# MB_RELAY.net
KiCad netlist of a schematic drawn in Altium Designer
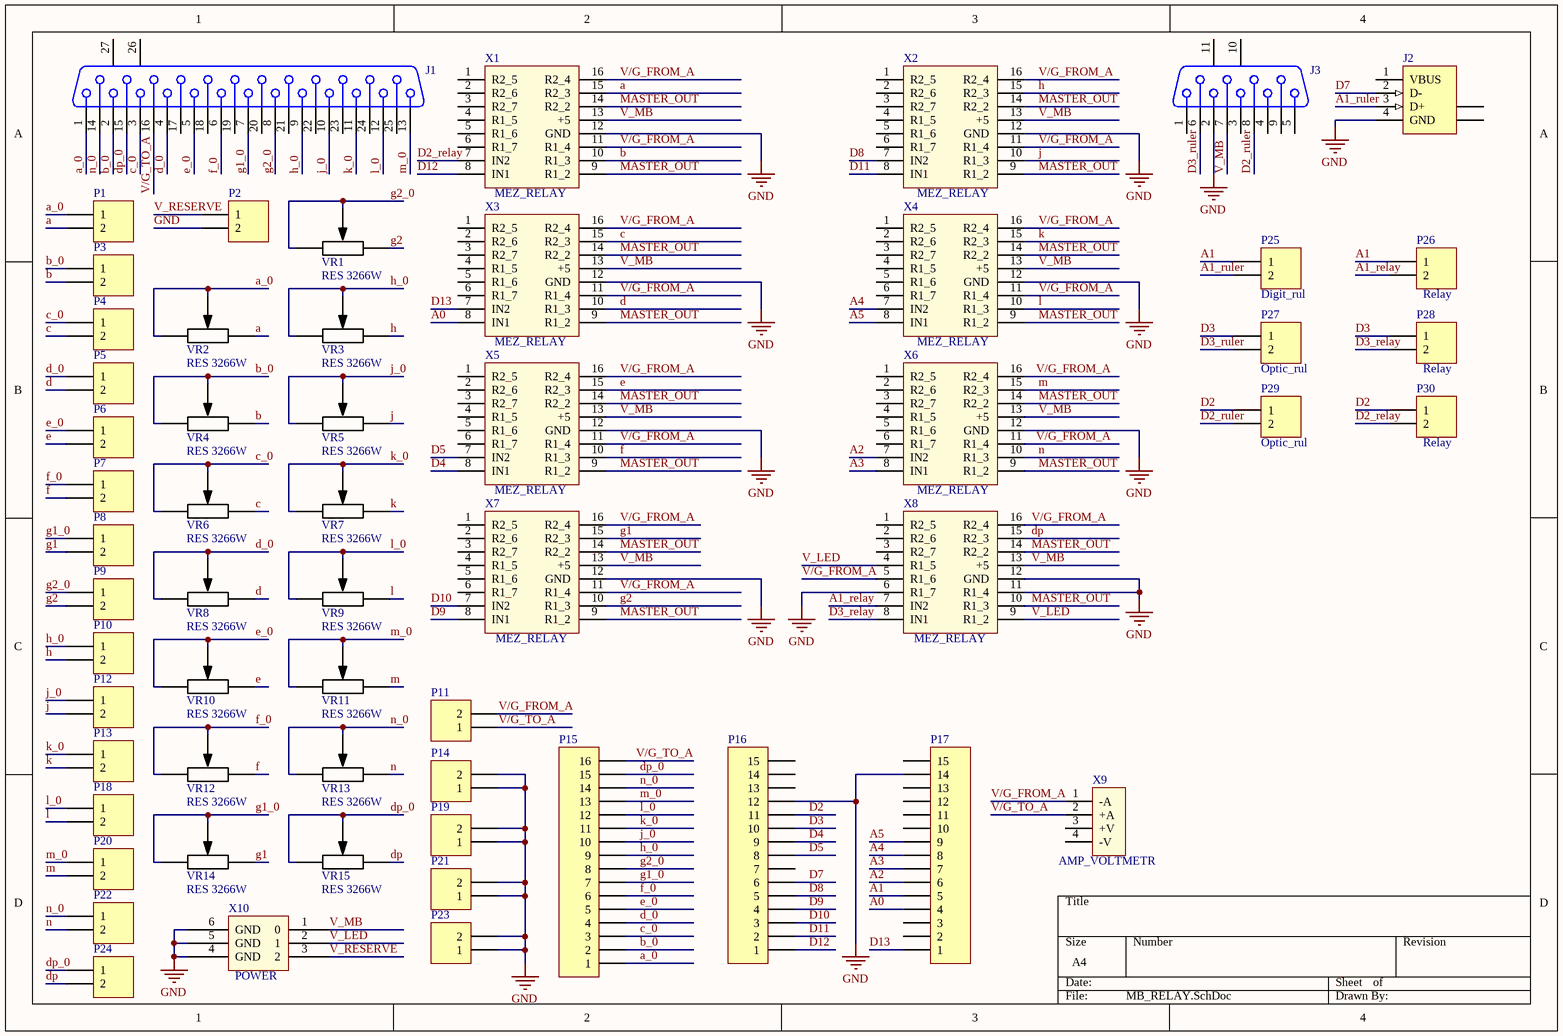
[diagram p0: MB_RELAY.SchDoc]

(export (version "E")
  (design (tool "Eeschema 10.0.6"))
  (components
    (comp (ref "J1")
      (value "D Connector 25")
      (footprint "DSUB1.385-2H25A")
      (description "Receptacle Assembly, 25 Position, Right Angle")
      (fields (field (name "PUBLISHER") "Altium Limited"))
      (libsource (lib "Miscellaneous Connectors") (part "D Connector 25"))
    )
    (comp (ref "J2")
      (value "1-353576-1")
      (footprint "353576")
      (description "USB 1.1, Right Angle, SMT, A Type, Receptacle, 4 Position, White")
      (fields (field (name "PUBLISHER") "Altium Limited"))
      (libsource (lib "AMP Serial Bus USB") (part "1-353576-1"))
    )
    (comp (ref "J3")
      (value "D Connector 9")
      (footprint "DSUB1.385-2H9")
      (description "Receptacle Assembly, 9 Position, Right Angle")
      (fields (field (name "PUBLISHER") "Altium Limited"))
      (libsource (lib "Miscellaneous Connectors") (part "D Connector 9"))
    )
    (comp (ref "P1")
      (value "Header 2")
      (footprint "HDR1X2")
      (description "Header, 2-Pin")
      (fields (field (name "PUBLISHER") "Altium Limited"))
      (libsource (lib "Miscellaneous Connectors") (part "Header 2"))
    )
    (comp (ref "P2")
      (value "Header 2")
      (footprint "HDR1X2")
      (description "Header, 2-Pin")
      (fields (field (name "PUBLISHER") "Altium Limited"))
      (libsource (lib "Miscellaneous Connectors") (part "Header 2"))
    )
    (comp (ref "P3")
      (value "Header 2")
      (footprint "HDR1X2")
      (description "Header, 2-Pin")
      (fields (field (name "PUBLISHER") "Altium Limited"))
      (libsource (lib "Miscellaneous Connectors") (part "Header 2"))
    )
    (comp (ref "P4")
      (value "Header 2")
      (footprint "HDR1X2")
      (description "Header, 2-Pin")
      (fields (field (name "PUBLISHER") "Altium Limited"))
      (libsource (lib "Miscellaneous Connectors") (part "Header 2"))
    )
    (comp (ref "P5")
      (value "Header 2")
      (footprint "HDR1X2")
      (description "Header, 2-Pin")
      (fields (field (name "PUBLISHER") "Altium Limited"))
      (libsource (lib "Miscellaneous Connectors") (part "Header 2"))
    )
    (comp (ref "P6")
      (value "GND")
      (footprint "HDR1X2")
      (description "Header, 2-Pin")
      (fields (field (name "PUBLISHER") "Altium Limited"))
      (libsource (lib "Miscellaneous Connectors") (part "Header 2"))
    )
    (comp (ref "P7")
      (value "GND")
      (footprint "HDR1X2")
      (description "Header, 2-Pin")
      (fields (field (name "PUBLISHER") "Altium Limited"))
      (libsource (lib "Miscellaneous Connectors") (part "Header 2"))
    )
    (comp (ref "P8")
      (value "GND")
      (footprint "HDR1X2")
      (description "Header, 2-Pin")
      (fields (field (name "PUBLISHER") "Altium Limited"))
      (libsource (lib "Miscellaneous Connectors") (part "Header 2"))
    )
    (comp (ref "P9")
      (value "GND")
      (footprint "HDR1X2")
      (description "Header, 2-Pin")
      (fields (field (name "PUBLISHER") "Altium Limited"))
      (libsource (lib "Miscellaneous Connectors") (part "Header 2"))
    )
    (comp (ref "P10")
      (value "Header 2")
      (footprint "HDR1X2")
      (description "Header, 2-Pin")
      (fields (field (name "PUBLISHER") "Altium Limited"))
      (libsource (lib "Miscellaneous Connectors") (part "Header 2"))
    )
    (comp (ref "P11")
      (value "Header 2")
      (footprint "HDR1X2")
      (description "Header, 2-Pin")
      (fields (field (name "PUBLISHER") "Altium Limited"))
      (libsource (lib "") (part "Header 2_1"))
    )
    (comp (ref "P12")
      (value "Header 2")
      (footprint "HDR1X2")
      (description "Header, 2-Pin")
      (fields (field (name "PUBLISHER") "Altium Limited"))
      (libsource (lib "Miscellaneous Connectors") (part "Header 2"))
    )
    (comp (ref "P13")
      (value "GND")
      (footprint "HDR1X2")
      (description "Header, 2-Pin")
      (fields (field (name "PUBLISHER") "Altium Limited"))
      (libsource (lib "Miscellaneous Connectors") (part "Header 2"))
    )
    (comp (ref "P14")
      (value "GND")
      (footprint "HDR1X2")
      (description "Header, 2-Pin")
      (fields (field (name "PUBLISHER") "Altium Limited"))
      (libsource (lib "") (part "Header 2_1"))
    )
    (comp (ref "P15")
      (value "Header 16")
      (footprint "HDR1X16")
      (description "Header, 16-Pin")
      (fields (field (name "PUBLISHER") "Altium Limited"))
      (libsource (lib "Miscellaneous Connectors") (part "Header 16"))
    )
    (comp (ref "P16")
      (value "Header 15")
      (footprint "HDR1X15")
      (description "Header, 15-Pin")
      (fields (field (name "PUBLISHER") "Altium Limited"))
      (libsource (lib "") (part "Header 15_1"))
    )
    (comp (ref "P17")
      (value "Header 15")
      (footprint "HDR1X15")
      (description "Header, 15-Pin")
      (fields (field (name "PUBLISHER") "Altium Limited"))
      (libsource (lib "Miscellaneous Connectors") (part "Header 15"))
    )
    (comp (ref "P18")
      (value "GND")
      (footprint "HDR1X2")
      (description "Header, 2-Pin")
      (fields (field (name "PUBLISHER") "Altium Limited"))
      (libsource (lib "Miscellaneous Connectors") (part "Header 2"))
    )
    (comp (ref "P19")
      (value "GND")
      (footprint "HDR1X2")
      (description "Header, 2-Pin")
      (fields (field (name "PUBLISHER") "Altium Limited"))
      (libsource (lib "") (part "Header 2_1"))
    )
    (comp (ref "P20")
      (value "GND")
      (footprint "HDR1X2")
      (description "Header, 2-Pin")
      (fields (field (name "PUBLISHER") "Altium Limited"))
      (libsource (lib "Miscellaneous Connectors") (part "Header 2"))
    )
    (comp (ref "P21")
      (value "GND")
      (footprint "HDR1X2")
      (description "Header, 2-Pin")
      (fields (field (name "PUBLISHER") "Altium Limited"))
      (libsource (lib "") (part "Header 2_1"))
    )
    (comp (ref "P22")
      (value "GND")
      (footprint "HDR1X2")
      (description "Header, 2-Pin")
      (fields (field (name "PUBLISHER") "Altium Limited"))
      (libsource (lib "Miscellaneous Connectors") (part "Header 2"))
    )
    (comp (ref "P23")
      (value "GND")
      (footprint "HDR1X2")
      (description "Header, 2-Pin")
      (fields (field (name "PUBLISHER") "Altium Limited"))
      (libsource (lib "") (part "Header 2_1"))
    )
    (comp (ref "P24")
      (value "GND")
      (footprint "HDR1X2")
      (description "Header, 2-Pin")
      (fields (field (name "PUBLISHER") "Altium Limited"))
      (libsource (lib "Miscellaneous Connectors") (part "Header 2"))
    )
    (comp (ref "P25")
      (value "Digit_rul")
      (footprint "HDR1X2")
      (description "Header, 2-Pin")
      (fields (field (name "PUBLISHER") "Altium Limited"))
      (libsource (lib "Miscellaneous Connectors") (part "Header 2"))
    )
    (comp (ref "P26")
      (value "Relay")
      (footprint "HDR1X2")
      (description "Header, 2-Pin")
      (fields (field (name "PUBLISHER") "Altium Limited"))
      (libsource (lib "Miscellaneous Connectors") (part "Header 2"))
    )
    (comp (ref "P27")
      (value "Optic_rul")
      (footprint "HDR1X2")
      (description "Header, 2-Pin")
      (fields (field (name "PUBLISHER") "Altium Limited"))
      (libsource (lib "Miscellaneous Connectors") (part "Header 2"))
    )
    (comp (ref "P28")
      (value "Relay")
      (footprint "HDR1X2")
      (description "Header, 2-Pin")
      (fields (field (name "PUBLISHER") "Altium Limited"))
      (libsource (lib "Miscellaneous Connectors") (part "Header 2"))
    )
    (comp (ref "P29")
      (value "Optic_rul")
      (footprint "HDR1X2")
      (description "Header, 2-Pin")
      (fields (field (name "PUBLISHER") "Altium Limited"))
      (libsource (lib "Miscellaneous Connectors") (part "Header 2"))
    )
    (comp (ref "P30")
      (value "Relay")
      (footprint "HDR1X2")
      (description "Header, 2-Pin")
      (fields (field (name "PUBLISHER") "Altium Limited"))
      (libsource (lib "Miscellaneous Connectors") (part "Header 2"))
    )
    (comp (ref "VR1")
      (value "RES 3266W")
      (footprint "aab_Passive:RES 3266W")
      (libsource (lib "aab_Schlib") (part "RES 3266W"))
    )
    (comp (ref "VR2")
      (value "RES 3266W")
      (footprint "aab_Passive:RES 3266W")
      (libsource (lib "aab_Schlib") (part "RES 3266W"))
    )
    (comp (ref "VR3")
      (value "RES 3266W")
      (footprint "aab_Passive:RES 3266W")
      (libsource (lib "aab_Schlib") (part "RES 3266W"))
    )
    (comp (ref "VR4")
      (value "RES 3266W")
      (footprint "aab_Passive:RES 3266W")
      (libsource (lib "aab_Schlib") (part "RES 3266W"))
    )
    (comp (ref "VR5")
      (value "RES 3266W")
      (footprint "aab_Passive:RES 3266W")
      (libsource (lib "aab_Schlib") (part "RES 3266W"))
    )
    (comp (ref "VR6")
      (value "RES 3266W")
      (footprint "aab_Passive:RES 3266W")
      (libsource (lib "aab_Schlib") (part "RES 3266W"))
    )
    (comp (ref "VR7")
      (value "RES 3266W")
      (footprint "aab_Passive:RES 3266W")
      (libsource (lib "aab_Schlib") (part "RES 3266W"))
    )
    (comp (ref "VR8")
      (value "RES 3266W")
      (footprint "aab_Passive:RES 3266W")
      (libsource (lib "aab_Schlib") (part "RES 3266W"))
    )
    (comp (ref "VR9")
      (value "RES 3266W")
      (footprint "aab_Passive:RES 3266W")
      (libsource (lib "aab_Schlib") (part "RES 3266W"))
    )
    (comp (ref "VR10")
      (value "RES 3266W")
      (footprint "aab_Passive:RES 3266W")
      (libsource (lib "aab_Schlib") (part "RES 3266W"))
    )
    (comp (ref "VR11")
      (value "RES 3266W")
      (footprint "aab_Passive:RES 3266W")
      (libsource (lib "aab_Schlib") (part "RES 3266W"))
    )
    (comp (ref "VR12")
      (value "RES 3266W")
      (footprint "aab_Passive:RES 3266W")
      (libsource (lib "aab_Schlib") (part "RES 3266W"))
    )
    (comp (ref "VR13")
      (value "RES 3266W")
      (footprint "aab_Passive:RES 3266W")
      (libsource (lib "aab_Schlib") (part "RES 3266W"))
    )
    (comp (ref "VR14")
      (value "RES 3266W")
      (footprint "aab_Passive:RES 3266W")
      (libsource (lib "aab_Schlib") (part "RES 3266W"))
    )
    (comp (ref "VR15")
      (value "RES 3266W")
      (footprint "aab_Passive:RES 3266W")
      (libsource (lib "aab_Schlib") (part "RES 3266W"))
    )
    (comp (ref "X1")
      (value "MEZ_RELAY")
      (footprint "MEZ_RELAY")
      (libsource (lib "msp_SchLib") (part "MEZ_RELAY"))
    )
    (comp (ref "X2")
      (value "MEZ_RELAY")
      (footprint "MEZ_RELAY")
      (libsource (lib "msp_SchLib") (part "MEZ_RELAY"))
    )
    (comp (ref "X3")
      (value "MEZ_RELAY")
      (footprint "MEZ_RELAY")
      (libsource (lib "msp_SchLib") (part "MEZ_RELAY"))
    )
    (comp (ref "X4")
      (value "MEZ_RELAY")
      (footprint "MEZ_RELAY")
      (libsource (lib "msp_SchLib") (part "MEZ_RELAY"))
    )
    (comp (ref "X5")
      (value "MEZ_RELAY")
      (footprint "MEZ_RELAY")
      (libsource (lib "msp_SchLib") (part "MEZ_RELAY"))
    )
    (comp (ref "X6")
      (value "MEZ_RELAY")
      (footprint "MEZ_RELAY")
      (libsource (lib "msp_SchLib") (part "MEZ_RELAY"))
    )
    (comp (ref "X7")
      (value "MEZ_RELAY")
      (footprint "MEZ_RELAY")
      (libsource (lib "msp_SchLib") (part "MEZ_RELAY"))
    )
    (comp (ref "X8")
      (value "MEZ_RELAY")
      (footprint "MEZ_RELAY")
      (libsource (lib "msp_SchLib") (part "MEZ_RELAY"))
    )
    (comp (ref "X9")
      (value "AMP_VOLTMETR")
      (footprint "vpl_Passive:AMP_VOLTMETER")
      (libsource (lib "msp_SchLib") (part "AMP_VOLTMETR"))
    )
    (comp (ref "X10")
      (value "POWER")
      (footprint "vpl_Passive:POWER")
      (libsource (lib "msp_SchLib") (part "POWER"))
    )
  )
  (nets
    (net (code "1") (name "/A0") (class "Default")
      (node (ref "P17") (pin "4") (pinfunction "4_4") (pintype "passive"))
      (node (ref "X3") (pin "8") (pinfunction "IN1_8") (pintype "passive"))
    )
    (net (code "2") (name "/A1") (class "Default")
      (node (ref "P17") (pin "5") (pinfunction "5_5") (pintype "passive"))
      (node (ref "P25") (pin "1") (pinfunction "1_1") (pintype "passive"))
      (node (ref "P26") (pin "1") (pinfunction "1_1") (pintype "passive"))
    )
    (net (code "3") (name "/A1_relay") (class "Default")
      (node (ref "P26") (pin "2") (pinfunction "2_2") (pintype "passive"))
      (node (ref "X8") (pin "7") (pinfunction "IN2_7") (pintype "passive"))
    )
    (net (code "4") (name "/A1_ruler") (class "Default")
      (node (ref "J2") (pin "3") (pinfunction "D+_3") (pintype "input"))
      (node (ref "P25") (pin "2") (pinfunction "2_2") (pintype "passive"))
    )
    (net (code "5") (name "/A2") (class "Default")
      (node (ref "P17") (pin "6") (pinfunction "6_6") (pintype "passive"))
      (node (ref "X6") (pin "7") (pinfunction "IN2_7") (pintype "passive"))
    )
    (net (code "6") (name "/A3") (class "Default")
      (node (ref "P17") (pin "7") (pinfunction "7_7") (pintype "passive"))
      (node (ref "X6") (pin "8") (pinfunction "IN1_8") (pintype "passive"))
    )
    (net (code "7") (name "/A4") (class "Default")
      (node (ref "P17") (pin "8") (pinfunction "8_8") (pintype "passive"))
      (node (ref "X4") (pin "7") (pinfunction "IN2_7") (pintype "passive"))
    )
    (net (code "8") (name "/A5") (class "Default")
      (node (ref "P17") (pin "9") (pinfunction "9_9") (pintype "passive"))
      (node (ref "X4") (pin "8") (pinfunction "IN1_8") (pintype "passive"))
    )
    (net (code "9") (name "/D2") (class "Default")
      (node (ref "P16") (pin "11") (pinfunction "11_11") (pintype "passive"))
      (node (ref "P29") (pin "1") (pinfunction "1_1") (pintype "passive"))
      (node (ref "P30") (pin "1") (pinfunction "1_1") (pintype "passive"))
    )
    (net (code "10") (name "/D2_relay") (class "Default")
      (node (ref "P30") (pin "2") (pinfunction "2_2") (pintype "passive"))
      (node (ref "X1") (pin "7") (pinfunction "IN2_7") (pintype "passive"))
    )
    (net (code "11") (name "/D2_ruler") (class "Default")
      (node (ref "J3") (pin "8") (pinfunction "8_8") (pintype "passive"))
      (node (ref "P29") (pin "2") (pinfunction "2_2") (pintype "passive"))
    )
    (net (code "12") (name "/D3") (class "Default")
      (node (ref "P16") (pin "10") (pinfunction "10_10") (pintype "passive"))
      (node (ref "P27") (pin "1") (pinfunction "1_1") (pintype "passive"))
      (node (ref "P28") (pin "1") (pinfunction "1_1") (pintype "passive"))
    )
    (net (code "13") (name "/D3_relay") (class "Default")
      (node (ref "P28") (pin "2") (pinfunction "2_2") (pintype "passive"))
      (node (ref "X8") (pin "8") (pinfunction "IN1_8") (pintype "passive"))
    )
    (net (code "14") (name "/D3_ruler") (class "Default")
      (node (ref "J3") (pin "6") (pinfunction "6_6") (pintype "passive"))
      (node (ref "P27") (pin "2") (pinfunction "2_2") (pintype "passive"))
    )
    (net (code "15") (name "/D4") (class "Default")
      (node (ref "P16") (pin "9") (pinfunction "9_9") (pintype "passive"))
      (node (ref "X5") (pin "8") (pinfunction "IN1_8") (pintype "passive"))
    )
    (net (code "16") (name "/D5") (class "Default")
      (node (ref "P16") (pin "8") (pinfunction "8_8") (pintype "passive"))
      (node (ref "X5") (pin "7") (pinfunction "IN2_7") (pintype "passive"))
    )
    (net (code "17") (name "/D7") (class "Default")
      (node (ref "J2") (pin "2") (pinfunction "D-_2") (pintype "input"))
      (node (ref "P16") (pin "6") (pinfunction "6_6") (pintype "passive"))
    )
    (net (code "18") (name "/D8") (class "Default")
      (node (ref "P16") (pin "5") (pinfunction "5_5") (pintype "passive"))
      (node (ref "X2") (pin "7") (pinfunction "IN2_7") (pintype "passive"))
    )
    (net (code "19") (name "/D9") (class "Default")
      (node (ref "P16") (pin "4") (pinfunction "4_4") (pintype "passive"))
      (node (ref "X7") (pin "8") (pinfunction "IN1_8") (pintype "passive"))
    )
    (net (code "20") (name "/D10") (class "Default")
      (node (ref "P16") (pin "3") (pinfunction "3_3") (pintype "passive"))
      (node (ref "X7") (pin "7") (pinfunction "IN2_7") (pintype "passive"))
    )
    (net (code "21") (name "/D11") (class "Default")
      (node (ref "P16") (pin "2") (pinfunction "2_2") (pintype "passive"))
      (node (ref "X2") (pin "8") (pinfunction "IN1_8") (pintype "passive"))
    )
    (net (code "22") (name "/D12") (class "Default")
      (node (ref "P16") (pin "1") (pinfunction "1_1") (pintype "passive"))
      (node (ref "X1") (pin "8") (pinfunction "IN1_8") (pintype "passive"))
    )
    (net (code "23") (name "/D13") (class "Default")
      (node (ref "P17") (pin "1") (pinfunction "1_1") (pintype "passive"))
      (node (ref "X3") (pin "7") (pinfunction "IN2_7") (pintype "passive"))
    )
    (net (code "24") (name "/MASTER_OUT") (class "Default")
      (node (ref "X1") (pin "14") (pinfunction "R2_2_14") (pintype "passive"))
      (node (ref "X1") (pin "9") (pinfunction "R1_2_9") (pintype "passive"))
      (node (ref "X2") (pin "14") (pinfunction "R2_2_14") (pintype "passive"))
      (node (ref "X2") (pin "9") (pinfunction "R1_2_9") (pintype "passive"))
      (node (ref "X3") (pin "14") (pinfunction "R2_2_14") (pintype "passive"))
      (node (ref "X3") (pin "9") (pinfunction "R1_2_9") (pintype "passive"))
      (node (ref "X4") (pin "14") (pinfunction "R2_2_14") (pintype "passive"))
      (node (ref "X4") (pin "9") (pinfunction "R1_2_9") (pintype "passive"))
      (node (ref "X5") (pin "14") (pinfunction "R2_2_14") (pintype "passive"))
      (node (ref "X5") (pin "9") (pinfunction "R1_2_9") (pintype "passive"))
      (node (ref "X6") (pin "14") (pinfunction "R2_2_14") (pintype "passive"))
      (node (ref "X6") (pin "9") (pinfunction "R1_2_9") (pintype "passive"))
      (node (ref "X7") (pin "14") (pinfunction "R2_2_14") (pintype "passive"))
      (node (ref "X7") (pin "9") (pinfunction "R1_2_9") (pintype "passive"))
      (node (ref "X8") (pin "10") (pinfunction "R1_3_10") (pintype "passive"))
      (node (ref "X8") (pin "14") (pinfunction "R2_2_14") (pintype "passive"))
    )
    (net (code "25") (name "/V_LED") (class "Default")
      (node (ref "X10") (pin "2") (pinfunction "1_2") (pintype "passive"))
      (node (ref "X8") (pin "4") (pinfunction "R1_5_4") (pintype "passive"))
      (node (ref "X8") (pin "9") (pinfunction "R1_2_9") (pintype "passive"))
    )
    (net (code "26") (name "/V_MB") (class "Default")
      (node (ref "J3") (pin "7") (pinfunction "7_7") (pintype "passive"))
      (node (ref "X1") (pin "13") (pinfunction "+5_13") (pintype "passive"))
      (node (ref "X10") (pin "1") (pinfunction "0_1") (pintype "passive"))
      (node (ref "X2") (pin "13") (pinfunction "+5_13") (pintype "passive"))
      (node (ref "X3") (pin "13") (pinfunction "+5_13") (pintype "passive"))
      (node (ref "X4") (pin "13") (pinfunction "+5_13") (pintype "passive"))
      (node (ref "X5") (pin "13") (pinfunction "+5_13") (pintype "passive"))
      (node (ref "X6") (pin "13") (pinfunction "+5_13") (pintype "passive"))
      (node (ref "X7") (pin "13") (pinfunction "+5_13") (pintype "passive"))
      (node (ref "X8") (pin "13") (pinfunction "+5_13") (pintype "passive"))
    )
    (net (code "27") (name "/V_RESERVE") (class "Default")
      (node (ref "P2") (pin "1") (pinfunction "1_1") (pintype "passive"))
      (node (ref "X10") (pin "3") (pinfunction "2_3") (pintype "passive"))
    )
    (net (code "28") (name "/V{slash}G_FROM_A") (class "Default")
      (node (ref "P11") (pin "2") (pinfunction "2_2") (pintype "passive"))
      (node (ref "X1") (pin "11") (pinfunction "R1_4_11") (pintype "passive"))
      (node (ref "X1") (pin "16") (pinfunction "R2_4_16") (pintype "passive"))
      (node (ref "X2") (pin "11") (pinfunction "R1_4_11") (pintype "passive"))
      (node (ref "X2") (pin "16") (pinfunction "R2_4_16") (pintype "passive"))
      (node (ref "X3") (pin "11") (pinfunction "R1_4_11") (pintype "passive"))
      (node (ref "X3") (pin "16") (pinfunction "R2_4_16") (pintype "passive"))
      (node (ref "X4") (pin "11") (pinfunction "R1_4_11") (pintype "passive"))
      (node (ref "X4") (pin "16") (pinfunction "R2_4_16") (pintype "passive"))
      (node (ref "X5") (pin "11") (pinfunction "R1_4_11") (pintype "passive"))
      (node (ref "X5") (pin "16") (pinfunction "R2_4_16") (pintype "passive"))
      (node (ref "X6") (pin "11") (pinfunction "R1_4_11") (pintype "passive"))
      (node (ref "X6") (pin "16") (pinfunction "R2_4_16") (pintype "passive"))
      (node (ref "X7") (pin "11") (pinfunction "R1_4_11") (pintype "passive"))
      (node (ref "X7") (pin "16") (pinfunction "R2_4_16") (pintype "passive"))
      (node (ref "X8") (pin "16") (pinfunction "R2_4_16") (pintype "passive"))
      (node (ref "X8") (pin "5") (pinfunction "R1_6_5") (pintype "passive"))
      (node (ref "X9") (pin "1") (pinfunction "-A_1") (pintype "passive"))
    )
    (net (code "29") (name "/V{slash}G_TO_A") (class "Default")
      (node (ref "J1") (pin "16") (pinfunction "16_16") (pintype "passive"))
      (node (ref "P11") (pin "1") (pinfunction "1_1") (pintype "passive"))
      (node (ref "P15") (pin "16") (pinfunction "16_16") (pintype "passive"))
      (node (ref "X9") (pin "2") (pinfunction "+A_2") (pintype "passive"))
    )
    (net (code "30") (name "/a") (class "Default")
      (node (ref "P1") (pin "2") (pinfunction "2_2") (pintype "passive"))
      (node (ref "VR2") (pin "3") (pinfunction "3_3") (pintype "passive"))
      (node (ref "X1") (pin "15") (pinfunction "R2_3_15") (pintype "passive"))
    )
    (net (code "31") (name "/a_0") (class "Default")
      (node (ref "J1") (pin "1") (pinfunction "1_1") (pintype "passive"))
      (node (ref "P1") (pin "1") (pinfunction "1_1") (pintype "passive"))
      (node (ref "P15") (pin "1") (pinfunction "1_1") (pintype "passive"))
      (node (ref "VR2") (pin "1") (pinfunction "1_1") (pintype "passive"))
      (node (ref "VR2") (pin "2") (pinfunction "2_2") (pintype "passive"))
    )
    (net (code "32") (name "/b") (class "Default")
      (node (ref "P3") (pin "2") (pinfunction "2_2") (pintype "passive"))
      (node (ref "VR4") (pin "3") (pinfunction "3_3") (pintype "passive"))
      (node (ref "X1") (pin "10") (pinfunction "R1_3_10") (pintype "passive"))
    )
    (net (code "33") (name "/b_0") (class "Default")
      (node (ref "J1") (pin "2") (pinfunction "2_2") (pintype "passive"))
      (node (ref "P15") (pin "2") (pinfunction "2_2") (pintype "passive"))
      (node (ref "P3") (pin "1") (pinfunction "1_1") (pintype "passive"))
      (node (ref "VR4") (pin "1") (pinfunction "1_1") (pintype "passive"))
      (node (ref "VR4") (pin "2") (pinfunction "2_2") (pintype "passive"))
    )
    (net (code "34") (name "/c") (class "Default")
      (node (ref "P4") (pin "2") (pinfunction "2_2") (pintype "passive"))
      (node (ref "VR6") (pin "3") (pinfunction "3_3") (pintype "passive"))
      (node (ref "X3") (pin "15") (pinfunction "R2_3_15") (pintype "passive"))
    )
    (net (code "35") (name "/c_0") (class "Default")
      (node (ref "J1") (pin "3") (pinfunction "3_3") (pintype "passive"))
      (node (ref "P15") (pin "3") (pinfunction "3_3") (pintype "passive"))
      (node (ref "P4") (pin "1") (pinfunction "1_1") (pintype "passive"))
      (node (ref "VR6") (pin "1") (pinfunction "1_1") (pintype "passive"))
      (node (ref "VR6") (pin "2") (pinfunction "2_2") (pintype "passive"))
    )
    (net (code "36") (name "/d") (class "Default")
      (node (ref "P5") (pin "2") (pinfunction "2_2") (pintype "passive"))
      (node (ref "VR8") (pin "3") (pinfunction "3_3") (pintype "passive"))
      (node (ref "X3") (pin "10") (pinfunction "R1_3_10") (pintype "passive"))
    )
    (net (code "37") (name "/d_0") (class "Default")
      (node (ref "J1") (pin "4") (pinfunction "4_4") (pintype "passive"))
      (node (ref "P15") (pin "4") (pinfunction "4_4") (pintype "passive"))
      (node (ref "P5") (pin "1") (pinfunction "1_1") (pintype "passive"))
      (node (ref "VR8") (pin "1") (pinfunction "1_1") (pintype "passive"))
      (node (ref "VR8") (pin "2") (pinfunction "2_2") (pintype "passive"))
    )
    (net (code "38") (name "/dp") (class "Default")
      (node (ref "P24") (pin "2") (pinfunction "2_2") (pintype "passive"))
      (node (ref "VR15") (pin "3") (pinfunction "3_3") (pintype "passive"))
      (node (ref "X8") (pin "15") (pinfunction "R2_3_15") (pintype "passive"))
    )
    (net (code "39") (name "/dp_0") (class "Default")
      (node (ref "J1") (pin "15") (pinfunction "15_15") (pintype "passive"))
      (node (ref "P15") (pin "15") (pinfunction "15_15") (pintype "passive"))
      (node (ref "P24") (pin "1") (pinfunction "1_1") (pintype "passive"))
      (node (ref "VR15") (pin "1") (pinfunction "1_1") (pintype "passive"))
      (node (ref "VR15") (pin "2") (pinfunction "2_2") (pintype "passive"))
    )
    (net (code "40") (name "/e") (class "Default")
      (node (ref "P6") (pin "2") (pinfunction "2_2") (pintype "passive"))
      (node (ref "VR10") (pin "3") (pinfunction "3_3") (pintype "passive"))
      (node (ref "X5") (pin "15") (pinfunction "R2_3_15") (pintype "passive"))
    )
    (net (code "41") (name "/e_0") (class "Default")
      (node (ref "J1") (pin "5") (pinfunction "5_5") (pintype "passive"))
      (node (ref "P15") (pin "5") (pinfunction "5_5") (pintype "passive"))
      (node (ref "P6") (pin "1") (pinfunction "1_1") (pintype "passive"))
      (node (ref "VR10") (pin "1") (pinfunction "1_1") (pintype "passive"))
      (node (ref "VR10") (pin "2") (pinfunction "2_2") (pintype "passive"))
    )
    (net (code "42") (name "/f") (class "Default")
      (node (ref "P7") (pin "2") (pinfunction "2_2") (pintype "passive"))
      (node (ref "VR12") (pin "3") (pinfunction "3_3") (pintype "passive"))
      (node (ref "X5") (pin "10") (pinfunction "R1_3_10") (pintype "passive"))
    )
    (net (code "43") (name "/f_0") (class "Default")
      (node (ref "J1") (pin "6") (pinfunction "6_6") (pintype "passive"))
      (node (ref "P15") (pin "6") (pinfunction "6_6") (pintype "passive"))
      (node (ref "P7") (pin "1") (pinfunction "1_1") (pintype "passive"))
      (node (ref "VR12") (pin "1") (pinfunction "1_1") (pintype "passive"))
      (node (ref "VR12") (pin "2") (pinfunction "2_2") (pintype "passive"))
    )
    (net (code "44") (name "/g1") (class "Default")
      (node (ref "P8") (pin "2") (pinfunction "2_2") (pintype "passive"))
      (node (ref "VR14") (pin "3") (pinfunction "3_3") (pintype "passive"))
      (node (ref "X7") (pin "15") (pinfunction "R2_3_15") (pintype "passive"))
    )
    (net (code "45") (name "/g1_0") (class "Default")
      (node (ref "J1") (pin "7") (pinfunction "7_7") (pintype "passive"))
      (node (ref "P15") (pin "7") (pinfunction "7_7") (pintype "passive"))
      (node (ref "P8") (pin "1") (pinfunction "1_1") (pintype "passive"))
      (node (ref "VR14") (pin "1") (pinfunction "1_1") (pintype "passive"))
      (node (ref "VR14") (pin "2") (pinfunction "2_2") (pintype "passive"))
    )
    (net (code "46") (name "/g2") (class "Default")
      (node (ref "P9") (pin "2") (pinfunction "2_2") (pintype "passive"))
      (node (ref "VR1") (pin "3") (pinfunction "3_3") (pintype "passive"))
      (node (ref "X7") (pin "10") (pinfunction "R1_3_10") (pintype "passive"))
    )
    (net (code "47") (name "/g2_0") (class "Default")
      (node (ref "J1") (pin "8") (pinfunction "8_8") (pintype "passive"))
      (node (ref "P15") (pin "8") (pinfunction "8_8") (pintype "passive"))
      (node (ref "P9") (pin "1") (pinfunction "1_1") (pintype "passive"))
      (node (ref "VR1") (pin "1") (pinfunction "1_1") (pintype "passive"))
      (node (ref "VR1") (pin "2") (pinfunction "2_2") (pintype "passive"))
    )
    (net (code "48") (name "/h") (class "Default")
      (node (ref "P10") (pin "2") (pinfunction "2_2") (pintype "passive"))
      (node (ref "VR3") (pin "3") (pinfunction "3_3") (pintype "passive"))
      (node (ref "X2") (pin "15") (pinfunction "R2_3_15") (pintype "passive"))
    )
    (net (code "49") (name "/h_0") (class "Default")
      (node (ref "J1") (pin "9") (pinfunction "9_9") (pintype "passive"))
      (node (ref "P10") (pin "1") (pinfunction "1_1") (pintype "passive"))
      (node (ref "P15") (pin "9") (pinfunction "9_9") (pintype "passive"))
      (node (ref "VR3") (pin "1") (pinfunction "1_1") (pintype "passive"))
      (node (ref "VR3") (pin "2") (pinfunction "2_2") (pintype "passive"))
    )
    (net (code "50") (name "/j") (class "Default")
      (node (ref "P12") (pin "2") (pinfunction "2_2") (pintype "passive"))
      (node (ref "VR5") (pin "3") (pinfunction "3_3") (pintype "passive"))
      (node (ref "X2") (pin "10") (pinfunction "R1_3_10") (pintype "passive"))
    )
    (net (code "51") (name "/j_0") (class "Default")
      (node (ref "J1") (pin "10") (pinfunction "10_10") (pintype "passive"))
      (node (ref "P12") (pin "1") (pinfunction "1_1") (pintype "passive"))
      (node (ref "P15") (pin "10") (pinfunction "10_10") (pintype "passive"))
      (node (ref "VR5") (pin "1") (pinfunction "1_1") (pintype "passive"))
      (node (ref "VR5") (pin "2") (pinfunction "2_2") (pintype "passive"))
    )
    (net (code "52") (name "/k") (class "Default")
      (node (ref "P13") (pin "2") (pinfunction "2_2") (pintype "passive"))
      (node (ref "VR7") (pin "3") (pinfunction "3_3") (pintype "passive"))
      (node (ref "X4") (pin "15") (pinfunction "R2_3_15") (pintype "passive"))
    )
    (net (code "53") (name "/k_0") (class "Default")
      (node (ref "J1") (pin "11") (pinfunction "11_11") (pintype "passive"))
      (node (ref "P13") (pin "1") (pinfunction "1_1") (pintype "passive"))
      (node (ref "P15") (pin "11") (pinfunction "11_11") (pintype "passive"))
      (node (ref "VR7") (pin "1") (pinfunction "1_1") (pintype "passive"))
      (node (ref "VR7") (pin "2") (pinfunction "2_2") (pintype "passive"))
    )
    (net (code "54") (name "/l") (class "Default")
      (node (ref "P18") (pin "2") (pinfunction "2_2") (pintype "passive"))
      (node (ref "VR9") (pin "3") (pinfunction "3_3") (pintype "passive"))
      (node (ref "X4") (pin "10") (pinfunction "R1_3_10") (pintype "passive"))
    )
    (net (code "55") (name "/l_0") (class "Default")
      (node (ref "J1") (pin "12") (pinfunction "12_12") (pintype "passive"))
      (node (ref "P15") (pin "12") (pinfunction "12_12") (pintype "passive"))
      (node (ref "P18") (pin "1") (pinfunction "1_1") (pintype "passive"))
      (node (ref "VR9") (pin "1") (pinfunction "1_1") (pintype "passive"))
      (node (ref "VR9") (pin "2") (pinfunction "2_2") (pintype "passive"))
    )
    (net (code "56") (name "/m") (class "Default")
      (node (ref "P20") (pin "2") (pinfunction "2_2") (pintype "passive"))
      (node (ref "VR11") (pin "3") (pinfunction "3_3") (pintype "passive"))
      (node (ref "X6") (pin "15") (pinfunction "R2_3_15") (pintype "passive"))
    )
    (net (code "57") (name "/m_0") (class "Default")
      (node (ref "J1") (pin "13") (pinfunction "13_13") (pintype "passive"))
      (node (ref "P15") (pin "13") (pinfunction "13_13") (pintype "passive"))
      (node (ref "P20") (pin "1") (pinfunction "1_1") (pintype "passive"))
      (node (ref "VR11") (pin "1") (pinfunction "1_1") (pintype "passive"))
      (node (ref "VR11") (pin "2") (pinfunction "2_2") (pintype "passive"))
    )
    (net (code "58") (name "/n") (class "Default")
      (node (ref "P22") (pin "2") (pinfunction "2_2") (pintype "passive"))
      (node (ref "VR13") (pin "3") (pinfunction "3_3") (pintype "passive"))
      (node (ref "X6") (pin "10") (pinfunction "R1_3_10") (pintype "passive"))
    )
    (net (code "59") (name "/n_0") (class "Default")
      (node (ref "J1") (pin "14") (pinfunction "14_14") (pintype "passive"))
      (node (ref "P15") (pin "14") (pinfunction "14_14") (pintype "passive"))
      (node (ref "P22") (pin "1") (pinfunction "1_1") (pintype "passive"))
      (node (ref "VR13") (pin "1") (pinfunction "1_1") (pintype "passive"))
      (node (ref "VR13") (pin "2") (pinfunction "2_2") (pintype "passive"))
    )
    (net (code "60") (name "GND") (class "Default")
      (node (ref "J2") (pin "4") (pinfunction "GND_4") (pintype "power_in"))
      (node (ref "J3") (pin "2") (pinfunction "2_2") (pintype "passive"))
      (node (ref "P14") (pin "1") (pinfunction "1_1") (pintype "passive"))
      (node (ref "P14") (pin "2") (pinfunction "2_2") (pintype "passive"))
      (node (ref "P16") (pin "12") (pinfunction "12_12") (pintype "passive"))
      (node (ref "P17") (pin "14") (pinfunction "14_14") (pintype "passive"))
      (node (ref "P19") (pin "1") (pinfunction "1_1") (pintype "passive"))
      (node (ref "P19") (pin "2") (pinfunction "2_2") (pintype "passive"))
      (node (ref "P2") (pin "2") (pinfunction "2_2") (pintype "passive"))
      (node (ref "P21") (pin "1") (pinfunction "1_1") (pintype "passive"))
      (node (ref "P21") (pin "2") (pinfunction "2_2") (pintype "passive"))
      (node (ref "P23") (pin "1") (pinfunction "1_1") (pintype "passive"))
      (node (ref "P23") (pin "2") (pinfunction "2_2") (pintype "passive"))
      (node (ref "X1") (pin "12") (pinfunction "GND_12") (pintype "passive"))
      (node (ref "X10") (pin "4") (pinfunction "GND_4") (pintype "passive"))
      (node (ref "X10") (pin "5") (pinfunction "GND_5") (pintype "passive"))
      (node (ref "X10") (pin "6") (pinfunction "GND_6") (pintype "passive"))
      (node (ref "X2") (pin "12") (pinfunction "GND_12") (pintype "passive"))
      (node (ref "X3") (pin "12") (pinfunction "GND_12") (pintype "passive"))
      (node (ref "X4") (pin "12") (pinfunction "GND_12") (pintype "passive"))
      (node (ref "X5") (pin "12") (pinfunction "GND_12") (pintype "passive"))
      (node (ref "X6") (pin "12") (pinfunction "GND_12") (pintype "passive"))
      (node (ref "X7") (pin "12") (pinfunction "GND_12") (pintype "passive"))
      (node (ref "X8") (pin "11") (pinfunction "R1_4_11") (pintype "passive"))
      (node (ref "X8") (pin "12") (pinfunction "GND_12") (pintype "passive"))
      (node (ref "X8") (pin "6") (pinfunction "R1_7_6") (pintype "passive"))
    )
    (net (code "61") (name "unconnected-(J1-MH1-Pad26)") (class "Default")
      (node (ref "J1") (pin "26") (pinfunction "MH1_26") (pintype "passive"))
    )
    (net (code "62") (name "unconnected-(J1-MH2-Pad27)") (class "Default")
      (node (ref "J1") (pin "27") (pinfunction "MH2_27") (pintype "passive"))
    )
    (net (code "63") (name "unconnected-(J1-Pad17)") (class "Default")
      (node (ref "J1") (pin "17") (pinfunction "17_17") (pintype "passive"))
    )
    (net (code "64") (name "unconnected-(J1-Pad18)") (class "Default")
      (node (ref "J1") (pin "18") (pinfunction "18_18") (pintype "passive"))
    )
    (net (code "65") (name "unconnected-(J1-Pad19)") (class "Default")
      (node (ref "J1") (pin "19") (pinfunction "19_19") (pintype "passive"))
    )
    (net (code "66") (name "unconnected-(J1-Pad20)") (class "Default")
      (node (ref "J1") (pin "20") (pinfunction "20_20") (pintype "passive"))
    )
    (net (code "67") (name "unconnected-(J1-Pad21)") (class "Default")
      (node (ref "J1") (pin "21") (pinfunction "21_21") (pintype "passive"))
    )
    (net (code "68") (name "unconnected-(J1-Pad22)") (class "Default")
      (node (ref "J1") (pin "22") (pinfunction "22_22") (pintype "passive"))
    )
    (net (code "69") (name "unconnected-(J1-Pad23)") (class "Default")
      (node (ref "J1") (pin "23") (pinfunction "23_23") (pintype "passive"))
    )
    (net (code "70") (name "unconnected-(J1-Pad24)") (class "Default")
      (node (ref "J1") (pin "24") (pinfunction "24_24") (pintype "passive"))
    )
    (net (code "71") (name "unconnected-(J1-Pad25)") (class "Default")
      (node (ref "J1") (pin "25") (pinfunction "25_25") (pintype "passive"))
    )
    (net (code "72") (name "unconnected-(J2-SHLD-Pad5)") (class "Default")
      (node (ref "J2") (pin "5") (pinfunction "SHLD_5") (pintype "passive"))
    )
    (net (code "73") (name "unconnected-(J2-SHLD-Pad6)") (class "Default")
      (node (ref "J2") (pin "6") (pinfunction "SHLD_6") (pintype "passive"))
    )
    (net (code "74") (name "unconnected-(J2-VBUS-Pad1)") (class "Default")
      (node (ref "J2") (pin "1") (pinfunction "VBUS_1") (pintype "power_in"))
    )
    (net (code "75") (name "unconnected-(J3-MH1-Pad10)") (class "Default")
      (node (ref "J3") (pin "10") (pinfunction "MH1_10") (pintype "passive"))
    )
    (net (code "76") (name "unconnected-(J3-MH2-Pad11)") (class "Default")
      (node (ref "J3") (pin "11") (pinfunction "MH2_11") (pintype "passive"))
    )
    (net (code "77") (name "unconnected-(J3-Pad1)") (class "Default")
      (node (ref "J3") (pin "1") (pinfunction "1_1") (pintype "passive"))
    )
    (net (code "78") (name "unconnected-(J3-Pad3)") (class "Default")
      (node (ref "J3") (pin "3") (pinfunction "3_3") (pintype "passive"))
    )
    (net (code "79") (name "unconnected-(J3-Pad4)") (class "Default")
      (node (ref "J3") (pin "4") (pinfunction "4_4") (pintype "passive"))
    )
    (net (code "80") (name "unconnected-(J3-Pad5)") (class "Default")
      (node (ref "J3") (pin "5") (pinfunction "5_5") (pintype "passive"))
    )
    (net (code "81") (name "unconnected-(J3-Pad9)") (class "Default")
      (node (ref "J3") (pin "9") (pinfunction "9_9") (pintype "passive"))
    )
    (net (code "82") (name "unconnected-(P16-Pad7)") (class "Default")
      (node (ref "P16") (pin "7") (pinfunction "7_7") (pintype "passive"))
    )
    (net (code "83") (name "unconnected-(P16-Pad13)") (class "Default")
      (node (ref "P16") (pin "13") (pinfunction "13_13") (pintype "passive"))
    )
    (net (code "84") (name "unconnected-(P16-Pad14)") (class "Default")
      (node (ref "P16") (pin "14") (pinfunction "14_14") (pintype "passive"))
    )
    (net (code "85") (name "unconnected-(P16-Pad15)") (class "Default")
      (node (ref "P16") (pin "15") (pinfunction "15_15") (pintype "passive"))
    )
    (net (code "86") (name "unconnected-(P17-Pad2)") (class "Default")
      (node (ref "P17") (pin "2") (pinfunction "2_2") (pintype "passive"))
    )
    (net (code "87") (name "unconnected-(P17-Pad3)") (class "Default")
      (node (ref "P17") (pin "3") (pinfunction "3_3") (pintype "passive"))
    )
    (net (code "88") (name "unconnected-(P17-Pad10)") (class "Default")
      (node (ref "P17") (pin "10") (pinfunction "10_10") (pintype "passive"))
    )
    (net (code "89") (name "unconnected-(P17-Pad11)") (class "Default")
      (node (ref "P17") (pin "11") (pinfunction "11_11") (pintype "passive"))
    )
    (net (code "90") (name "unconnected-(P17-Pad12)") (class "Default")
      (node (ref "P17") (pin "12") (pinfunction "12_12") (pintype "passive"))
    )
    (net (code "91") (name "unconnected-(P17-Pad13)") (class "Default")
      (node (ref "P17") (pin "13") (pinfunction "13_13") (pintype "passive"))
    )
    (net (code "92") (name "unconnected-(P17-Pad15)") (class "Default")
      (node (ref "P17") (pin "15") (pinfunction "15_15") (pintype "passive"))
    )
    (net (code "93") (name "unconnected-(X1-R1_5-Pad4)") (class "Default")
      (node (ref "X1") (pin "4") (pinfunction "R1_5_4") (pintype "passive"))
    )
    (net (code "94") (name "unconnected-(X1-R1_6-Pad5)") (class "Default")
      (node (ref "X1") (pin "5") (pinfunction "R1_6_5") (pintype "passive"))
    )
    (net (code "95") (name "unconnected-(X1-R1_7-Pad6)") (class "Default")
      (node (ref "X1") (pin "6") (pinfunction "R1_7_6") (pintype "passive"))
    )
    (net (code "96") (name "unconnected-(X1-R2_5-Pad1)") (class "Default")
      (node (ref "X1") (pin "1") (pinfunction "R2_5_1") (pintype "passive"))
    )
    (net (code "97") (name "unconnected-(X1-R2_6-Pad2)") (class "Default")
      (node (ref "X1") (pin "2") (pinfunction "R2_6_2") (pintype "passive"))
    )
    (net (code "98") (name "unconnected-(X1-R2_7-Pad3)") (class "Default")
      (node (ref "X1") (pin "3") (pinfunction "R2_7_3") (pintype "passive"))
    )
    (net (code "99") (name "unconnected-(X2-R1_5-Pad4)") (class "Default")
      (node (ref "X2") (pin "4") (pinfunction "R1_5_4") (pintype "passive"))
    )
    (net (code "100") (name "unconnected-(X2-R1_6-Pad5)") (class "Default")
      (node (ref "X2") (pin "5") (pinfunction "R1_6_5") (pintype "passive"))
    )
    (net (code "101") (name "unconnected-(X2-R1_7-Pad6)") (class "Default")
      (node (ref "X2") (pin "6") (pinfunction "R1_7_6") (pintype "passive"))
    )
    (net (code "102") (name "unconnected-(X2-R2_5-Pad1)") (class "Default")
      (node (ref "X2") (pin "1") (pinfunction "R2_5_1") (pintype "passive"))
    )
    (net (code "103") (name "unconnected-(X2-R2_6-Pad2)") (class "Default")
      (node (ref "X2") (pin "2") (pinfunction "R2_6_2") (pintype "passive"))
    )
    (net (code "104") (name "unconnected-(X2-R2_7-Pad3)") (class "Default")
      (node (ref "X2") (pin "3") (pinfunction "R2_7_3") (pintype "passive"))
    )
    (net (code "105") (name "unconnected-(X3-R1_5-Pad4)") (class "Default")
      (node (ref "X3") (pin "4") (pinfunction "R1_5_4") (pintype "passive"))
    )
    (net (code "106") (name "unconnected-(X3-R1_6-Pad5)") (class "Default")
      (node (ref "X3") (pin "5") (pinfunction "R1_6_5") (pintype "passive"))
    )
    (net (code "107") (name "unconnected-(X3-R1_7-Pad6)") (class "Default")
      (node (ref "X3") (pin "6") (pinfunction "R1_7_6") (pintype "passive"))
    )
    (net (code "108") (name "unconnected-(X3-R2_5-Pad1)") (class "Default")
      (node (ref "X3") (pin "1") (pinfunction "R2_5_1") (pintype "passive"))
    )
    (net (code "109") (name "unconnected-(X3-R2_6-Pad2)") (class "Default")
      (node (ref "X3") (pin "2") (pinfunction "R2_6_2") (pintype "passive"))
    )
    (net (code "110") (name "unconnected-(X3-R2_7-Pad3)") (class "Default")
      (node (ref "X3") (pin "3") (pinfunction "R2_7_3") (pintype "passive"))
    )
    (net (code "111") (name "unconnected-(X4-R1_5-Pad4)") (class "Default")
      (node (ref "X4") (pin "4") (pinfunction "R1_5_4") (pintype "passive"))
    )
    (net (code "112") (name "unconnected-(X4-R1_6-Pad5)") (class "Default")
      (node (ref "X4") (pin "5") (pinfunction "R1_6_5") (pintype "passive"))
    )
    (net (code "113") (name "unconnected-(X4-R1_7-Pad6)") (class "Default")
      (node (ref "X4") (pin "6") (pinfunction "R1_7_6") (pintype "passive"))
    )
    (net (code "114") (name "unconnected-(X4-R2_5-Pad1)") (class "Default")
      (node (ref "X4") (pin "1") (pinfunction "R2_5_1") (pintype "passive"))
    )
    (net (code "115") (name "unconnected-(X4-R2_6-Pad2)") (class "Default")
      (node (ref "X4") (pin "2") (pinfunction "R2_6_2") (pintype "passive"))
    )
    (net (code "116") (name "unconnected-(X4-R2_7-Pad3)") (class "Default")
      (node (ref "X4") (pin "3") (pinfunction "R2_7_3") (pintype "passive"))
    )
    (net (code "117") (name "unconnected-(X5-R1_5-Pad4)") (class "Default")
      (node (ref "X5") (pin "4") (pinfunction "R1_5_4") (pintype "passive"))
    )
    (net (code "118") (name "unconnected-(X5-R1_6-Pad5)") (class "Default")
      (node (ref "X5") (pin "5") (pinfunction "R1_6_5") (pintype "passive"))
    )
    (net (code "119") (name "unconnected-(X5-R1_7-Pad6)") (class "Default")
      (node (ref "X5") (pin "6") (pinfunction "R1_7_6") (pintype "passive"))
    )
    (net (code "120") (name "unconnected-(X5-R2_5-Pad1)") (class "Default")
      (node (ref "X5") (pin "1") (pinfunction "R2_5_1") (pintype "passive"))
    )
    (net (code "121") (name "unconnected-(X5-R2_6-Pad2)") (class "Default")
      (node (ref "X5") (pin "2") (pinfunction "R2_6_2") (pintype "passive"))
    )
    (net (code "122") (name "unconnected-(X5-R2_7-Pad3)") (class "Default")
      (node (ref "X5") (pin "3") (pinfunction "R2_7_3") (pintype "passive"))
    )
    (net (code "123") (name "unconnected-(X6-R1_5-Pad4)") (class "Default")
      (node (ref "X6") (pin "4") (pinfunction "R1_5_4") (pintype "passive"))
    )
    (net (code "124") (name "unconnected-(X6-R1_6-Pad5)") (class "Default")
      (node (ref "X6") (pin "5") (pinfunction "R1_6_5") (pintype "passive"))
    )
    (net (code "125") (name "unconnected-(X6-R1_7-Pad6)") (class "Default")
      (node (ref "X6") (pin "6") (pinfunction "R1_7_6") (pintype "passive"))
    )
    (net (code "126") (name "unconnected-(X6-R2_5-Pad1)") (class "Default")
      (node (ref "X6") (pin "1") (pinfunction "R2_5_1") (pintype "passive"))
    )
    (net (code "127") (name "unconnected-(X6-R2_6-Pad2)") (class "Default")
      (node (ref "X6") (pin "2") (pinfunction "R2_6_2") (pintype "passive"))
    )
    (net (code "128") (name "unconnected-(X6-R2_7-Pad3)") (class "Default")
      (node (ref "X6") (pin "3") (pinfunction "R2_7_3") (pintype "passive"))
    )
    (net (code "129") (name "unconnected-(X7-R1_5-Pad4)") (class "Default")
      (node (ref "X7") (pin "4") (pinfunction "R1_5_4") (pintype "passive"))
    )
    (net (code "130") (name "unconnected-(X7-R1_6-Pad5)") (class "Default")
      (node (ref "X7") (pin "5") (pinfunction "R1_6_5") (pintype "passive"))
    )
    (net (code "131") (name "unconnected-(X7-R1_7-Pad6)") (class "Default")
      (node (ref "X7") (pin "6") (pinfunction "R1_7_6") (pintype "passive"))
    )
    (net (code "132") (name "unconnected-(X7-R2_5-Pad1)") (class "Default")
      (node (ref "X7") (pin "1") (pinfunction "R2_5_1") (pintype "passive"))
    )
    (net (code "133") (name "unconnected-(X7-R2_6-Pad2)") (class "Default")
      (node (ref "X7") (pin "2") (pinfunction "R2_6_2") (pintype "passive"))
    )
    (net (code "134") (name "unconnected-(X7-R2_7-Pad3)") (class "Default")
      (node (ref "X7") (pin "3") (pinfunction "R2_7_3") (pintype "passive"))
    )
    (net (code "135") (name "unconnected-(X8-R2_5-Pad1)") (class "Default")
      (node (ref "X8") (pin "1") (pinfunction "R2_5_1") (pintype "passive"))
    )
    (net (code "136") (name "unconnected-(X8-R2_6-Pad2)") (class "Default")
      (node (ref "X8") (pin "2") (pinfunction "R2_6_2") (pintype "passive"))
    )
    (net (code "137") (name "unconnected-(X8-R2_7-Pad3)") (class "Default")
      (node (ref "X8") (pin "3") (pinfunction "R2_7_3") (pintype "passive"))
    )
    (net (code "138") (name "unconnected-(X9-+V-Pad3)") (class "Default")
      (node (ref "X9") (pin "3") (pinfunction "+V_3") (pintype "passive"))
    )
    (net (code "139") (name "unconnected-(X9--V-Pad4)") (class "Default")
      (node (ref "X9") (pin "4") (pinfunction "-V_4") (pintype "passive"))
    )
  )
)
